# Schaltplan-LED.net
KiCad netlist of a schematic drawn in EAGLE
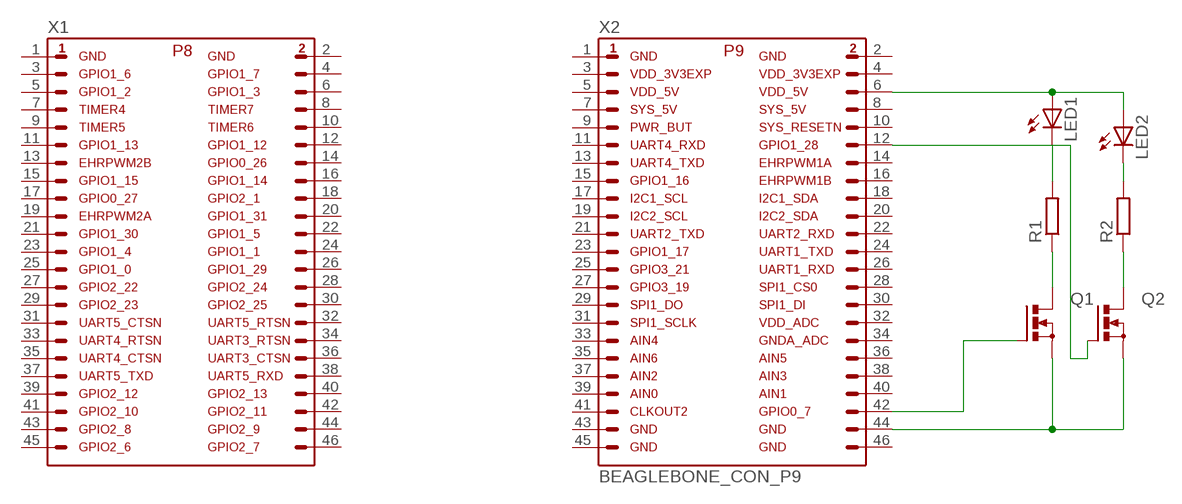
[diagram p0: schematic, sheet 1]

(export (version "E")
  (design (tool "Eeschema 10.0.6"))
  (components
    (comp (ref "LED1")
      (value "LEDCHIP-LED0603")
      (footprint "eagle-import:CHIP-LED0603")
      (libsource (lib "eagle-import") (part "LEDCHIP-LED0603"))
    )
    (comp (ref "LED2")
      (value "LEDCHIP-LED0603")
      (footprint "eagle-import:CHIP-LED0603")
      (libsource (lib "eagle-import") (part "LEDCHIP-LED0603"))
    )
    (comp (ref "Q1")
      (value "N-MOSFET-SO8S")
      (footprint "eagle-import:SO-08")
      (libsource (lib "eagle-import") (part "N-MOSFET-SO8S"))
    )
    (comp (ref "Q2")
      (value "N-MOSFET-SO8S")
      (footprint "eagle-import:SO-08")
      (libsource (lib "eagle-import") (part "N-MOSFET-SO8S"))
    )
    (comp (ref "R1")
      (value "R-EU_R0603")
      (footprint "eagle-import:R0603")
      (libsource (lib "eagle-import") (part "R-EU_R0603"))
    )
    (comp (ref "R2")
      (value "R-EU_R0603")
      (footprint "eagle-import:R0603")
      (libsource (lib "eagle-import") (part "R-EU_R0603"))
    )
    (comp (ref "X1")
      (value "BEAGLEBONE_CON_P8")
      (footprint "eagle-import:23X2_2-54")
      (libsource (lib "eagle-import") (part "BEAGLEBONE_CON_P8"))
    )
    (comp (ref "X2")
      (value "BEAGLEBONE_CON_P9")
      (footprint "eagle-import:23X2_2-54")
      (libsource (lib "eagle-import") (part "BEAGLEBONE_CON_P9"))
    )
  )
  (nets
    (net (code "1") (name "Net-(LED1-PadA)") (class "Default")
      (node (ref "LED1") (pin "A") (pinfunction "A_A") (pintype "passive"))
      (node (ref "LED2") (pin "A") (pinfunction "A_A") (pintype "passive"))
      (node (ref "X2") (pin "6") (pinfunction "6_6") (pintype "passive"))
    )
    (net (code "2") (name "Net-(LED1-PadC)") (class "Default")
      (node (ref "LED1") (pin "C") (pinfunction "C_C") (pintype "passive"))
      (node (ref "R1") (pin "2") (pinfunction "2_2") (pintype "passive"))
    )
    (net (code "3") (name "Net-(LED2-PadC)") (class "Default")
      (node (ref "LED2") (pin "C") (pinfunction "C_C") (pintype "passive"))
      (node (ref "R2") (pin "2") (pinfunction "2_2") (pintype "passive"))
    )
    (net (code "4") (name "Net-(Q1-D-Pad5)") (class "Default")
      (node (ref "Q1") (pin "5") (pinfunction "D_5") (pintype "passive"))
      (node (ref "Q1") (pin "6") (pinfunction "D_6") (pintype "passive"))
      (node (ref "Q1") (pin "7") (pinfunction "D_7") (pintype "passive"))
      (node (ref "Q1") (pin "8") (pinfunction "D_8") (pintype "passive"))
      (node (ref "R1") (pin "1") (pinfunction "1_1") (pintype "passive"))
    )
    (net (code "5") (name "Net-(Q1-G)") (class "Default")
      (node (ref "Q1") (pin "4") (pinfunction "G_4") (pintype "passive"))
      (node (ref "X2") (pin "42") (pinfunction "42_42") (pintype "passive"))
    )
    (net (code "6") (name "Net-(Q1-S-Pad1)") (class "Default")
      (node (ref "Q1") (pin "1") (pinfunction "S_1") (pintype "passive"))
      (node (ref "Q1") (pin "2") (pinfunction "S_2") (pintype "passive"))
      (node (ref "Q1") (pin "3") (pinfunction "S_3") (pintype "passive"))
      (node (ref "Q2") (pin "1") (pinfunction "S_1") (pintype "passive"))
      (node (ref "Q2") (pin "2") (pinfunction "S_2") (pintype "passive"))
      (node (ref "Q2") (pin "3") (pinfunction "S_3") (pintype "passive"))
      (node (ref "X2") (pin "44") (pinfunction "44_44") (pintype "passive"))
    )
    (net (code "7") (name "Net-(Q2-D-Pad5)") (class "Default")
      (node (ref "Q2") (pin "5") (pinfunction "D_5") (pintype "passive"))
      (node (ref "Q2") (pin "6") (pinfunction "D_6") (pintype "passive"))
      (node (ref "Q2") (pin "7") (pinfunction "D_7") (pintype "passive"))
      (node (ref "Q2") (pin "8") (pinfunction "D_8") (pintype "passive"))
      (node (ref "R2") (pin "1") (pinfunction "1_1") (pintype "passive"))
    )
    (net (code "8") (name "Net-(Q2-G)") (class "Default")
      (node (ref "Q2") (pin "4") (pinfunction "G_4") (pintype "passive"))
      (node (ref "X2") (pin "12") (pinfunction "12_12") (pintype "passive"))
    )
    (net (code "9") (name "unconnected-(X1-Pad1)") (class "Default")
      (node (ref "X1") (pin "1") (pinfunction "1_1") (pintype "passive"))
    )
    (net (code "10") (name "unconnected-(X1-Pad2)") (class "Default")
      (node (ref "X1") (pin "2") (pinfunction "2_2") (pintype "passive"))
    )
    (net (code "11") (name "unconnected-(X1-Pad3)") (class "Default")
      (node (ref "X1") (pin "3") (pinfunction "3_3") (pintype "passive"))
    )
    (net (code "12") (name "unconnected-(X1-Pad4)") (class "Default")
      (node (ref "X1") (pin "4") (pinfunction "4_4") (pintype "passive"))
    )
    (net (code "13") (name "unconnected-(X1-Pad5)") (class "Default")
      (node (ref "X1") (pin "5") (pinfunction "5_5") (pintype "passive"))
    )
    (net (code "14") (name "unconnected-(X1-Pad6)") (class "Default")
      (node (ref "X1") (pin "6") (pinfunction "6_6") (pintype "passive"))
    )
    (net (code "15") (name "unconnected-(X1-Pad7)") (class "Default")
      (node (ref "X1") (pin "7") (pinfunction "7_7") (pintype "passive"))
    )
    (net (code "16") (name "unconnected-(X1-Pad8)") (class "Default")
      (node (ref "X1") (pin "8") (pinfunction "8_8") (pintype "passive"))
    )
    (net (code "17") (name "unconnected-(X1-Pad9)") (class "Default")
      (node (ref "X1") (pin "9") (pinfunction "9_9") (pintype "passive"))
    )
    (net (code "18") (name "unconnected-(X1-Pad10)") (class "Default")
      (node (ref "X1") (pin "10") (pinfunction "10_10") (pintype "passive"))
    )
    (net (code "19") (name "unconnected-(X1-Pad11)") (class "Default")
      (node (ref "X1") (pin "11") (pinfunction "11_11") (pintype "passive"))
    )
    (net (code "20") (name "unconnected-(X1-Pad12)") (class "Default")
      (node (ref "X1") (pin "12") (pinfunction "12_12") (pintype "passive"))
    )
    (net (code "21") (name "unconnected-(X1-Pad13)") (class "Default")
      (node (ref "X1") (pin "13") (pinfunction "13_13") (pintype "passive"))
    )
    (net (code "22") (name "unconnected-(X1-Pad14)") (class "Default")
      (node (ref "X1") (pin "14") (pinfunction "14_14") (pintype "passive"))
    )
    (net (code "23") (name "unconnected-(X1-Pad15)") (class "Default")
      (node (ref "X1") (pin "15") (pinfunction "15_15") (pintype "passive"))
    )
    (net (code "24") (name "unconnected-(X1-Pad16)") (class "Default")
      (node (ref "X1") (pin "16") (pinfunction "16_16") (pintype "passive"))
    )
    (net (code "25") (name "unconnected-(X1-Pad17)") (class "Default")
      (node (ref "X1") (pin "17") (pinfunction "17_17") (pintype "passive"))
    )
    (net (code "26") (name "unconnected-(X1-Pad18)") (class "Default")
      (node (ref "X1") (pin "18") (pinfunction "18_18") (pintype "passive"))
    )
    (net (code "27") (name "unconnected-(X1-Pad19)") (class "Default")
      (node (ref "X1") (pin "19") (pinfunction "19_19") (pintype "passive"))
    )
    (net (code "28") (name "unconnected-(X1-Pad20)") (class "Default")
      (node (ref "X1") (pin "20") (pinfunction "20_20") (pintype "passive"))
    )
    (net (code "29") (name "unconnected-(X1-Pad21)") (class "Default")
      (node (ref "X1") (pin "21") (pinfunction "21_21") (pintype "passive"))
    )
    (net (code "30") (name "unconnected-(X1-Pad22)") (class "Default")
      (node (ref "X1") (pin "22") (pinfunction "22_22") (pintype "passive"))
    )
    (net (code "31") (name "unconnected-(X1-Pad23)") (class "Default")
      (node (ref "X1") (pin "23") (pinfunction "23_23") (pintype "passive"))
    )
    (net (code "32") (name "unconnected-(X1-Pad24)") (class "Default")
      (node (ref "X1") (pin "24") (pinfunction "24_24") (pintype "passive"))
    )
    (net (code "33") (name "unconnected-(X1-Pad25)") (class "Default")
      (node (ref "X1") (pin "25") (pinfunction "25_25") (pintype "passive"))
    )
    (net (code "34") (name "unconnected-(X1-Pad26)") (class "Default")
      (node (ref "X1") (pin "26") (pinfunction "26_26") (pintype "passive"))
    )
    (net (code "35") (name "unconnected-(X1-Pad27)") (class "Default")
      (node (ref "X1") (pin "27") (pinfunction "27_27") (pintype "passive"))
    )
    (net (code "36") (name "unconnected-(X1-Pad28)") (class "Default")
      (node (ref "X1") (pin "28") (pinfunction "28_28") (pintype "passive"))
    )
    (net (code "37") (name "unconnected-(X1-Pad29)") (class "Default")
      (node (ref "X1") (pin "29") (pinfunction "29_29") (pintype "passive"))
    )
    (net (code "38") (name "unconnected-(X1-Pad30)") (class "Default")
      (node (ref "X1") (pin "30") (pinfunction "30_30") (pintype "passive"))
    )
    (net (code "39") (name "unconnected-(X1-Pad31)") (class "Default")
      (node (ref "X1") (pin "31") (pinfunction "31_31") (pintype "passive"))
    )
    (net (code "40") (name "unconnected-(X1-Pad32)") (class "Default")
      (node (ref "X1") (pin "32") (pinfunction "32_32") (pintype "passive"))
    )
    (net (code "41") (name "unconnected-(X1-Pad33)") (class "Default")
      (node (ref "X1") (pin "33") (pinfunction "33_33") (pintype "passive"))
    )
    (net (code "42") (name "unconnected-(X1-Pad34)") (class "Default")
      (node (ref "X1") (pin "34") (pinfunction "34_34") (pintype "passive"))
    )
    (net (code "43") (name "unconnected-(X1-Pad35)") (class "Default")
      (node (ref "X1") (pin "35") (pinfunction "35_35") (pintype "passive"))
    )
    (net (code "44") (name "unconnected-(X1-Pad36)") (class "Default")
      (node (ref "X1") (pin "36") (pinfunction "36_36") (pintype "passive"))
    )
    (net (code "45") (name "unconnected-(X1-Pad37)") (class "Default")
      (node (ref "X1") (pin "37") (pinfunction "37_37") (pintype "passive"))
    )
    (net (code "46") (name "unconnected-(X1-Pad38)") (class "Default")
      (node (ref "X1") (pin "38") (pinfunction "38_38") (pintype "passive"))
    )
    (net (code "47") (name "unconnected-(X1-Pad39)") (class "Default")
      (node (ref "X1") (pin "39") (pinfunction "39_39") (pintype "passive"))
    )
    (net (code "48") (name "unconnected-(X1-Pad40)") (class "Default")
      (node (ref "X1") (pin "40") (pinfunction "40_40") (pintype "passive"))
    )
    (net (code "49") (name "unconnected-(X1-Pad41)") (class "Default")
      (node (ref "X1") (pin "41") (pinfunction "41_41") (pintype "passive"))
    )
    (net (code "50") (name "unconnected-(X1-Pad42)") (class "Default")
      (node (ref "X1") (pin "42") (pinfunction "42_42") (pintype "passive"))
    )
    (net (code "51") (name "unconnected-(X1-Pad43)") (class "Default")
      (node (ref "X1") (pin "43") (pinfunction "43_43") (pintype "passive"))
    )
    (net (code "52") (name "unconnected-(X1-Pad44)") (class "Default")
      (node (ref "X1") (pin "44") (pinfunction "44_44") (pintype "passive"))
    )
    (net (code "53") (name "unconnected-(X1-Pad45)") (class "Default")
      (node (ref "X1") (pin "45") (pinfunction "45_45") (pintype "passive"))
    )
    (net (code "54") (name "unconnected-(X1-Pad46)") (class "Default")
      (node (ref "X1") (pin "46") (pinfunction "46_46") (pintype "passive"))
    )
    (net (code "55") (name "unconnected-(X2-Pad1)") (class "Default")
      (node (ref "X2") (pin "1") (pinfunction "1_1") (pintype "passive"))
    )
    (net (code "56") (name "unconnected-(X2-Pad2)") (class "Default")
      (node (ref "X2") (pin "2") (pinfunction "2_2") (pintype "passive"))
    )
    (net (code "57") (name "unconnected-(X2-Pad3)") (class "Default")
      (node (ref "X2") (pin "3") (pinfunction "3_3") (pintype "passive"))
    )
    (net (code "58") (name "unconnected-(X2-Pad4)") (class "Default")
      (node (ref "X2") (pin "4") (pinfunction "4_4") (pintype "passive"))
    )
    (net (code "59") (name "unconnected-(X2-Pad5)") (class "Default")
      (node (ref "X2") (pin "5") (pinfunction "5_5") (pintype "passive"))
    )
    (net (code "60") (name "unconnected-(X2-Pad7)") (class "Default")
      (node (ref "X2") (pin "7") (pinfunction "7_7") (pintype "passive"))
    )
    (net (code "61") (name "unconnected-(X2-Pad8)") (class "Default")
      (node (ref "X2") (pin "8") (pinfunction "8_8") (pintype "passive"))
    )
    (net (code "62") (name "unconnected-(X2-Pad9)") (class "Default")
      (node (ref "X2") (pin "9") (pinfunction "9_9") (pintype "passive"))
    )
    (net (code "63") (name "unconnected-(X2-Pad10)") (class "Default")
      (node (ref "X2") (pin "10") (pinfunction "10_10") (pintype "passive"))
    )
    (net (code "64") (name "unconnected-(X2-Pad11)") (class "Default")
      (node (ref "X2") (pin "11") (pinfunction "11_11") (pintype "passive"))
    )
    (net (code "65") (name "unconnected-(X2-Pad13)") (class "Default")
      (node (ref "X2") (pin "13") (pinfunction "13_13") (pintype "passive"))
    )
    (net (code "66") (name "unconnected-(X2-Pad14)") (class "Default")
      (node (ref "X2") (pin "14") (pinfunction "14_14") (pintype "passive"))
    )
    (net (code "67") (name "unconnected-(X2-Pad15)") (class "Default")
      (node (ref "X2") (pin "15") (pinfunction "15_15") (pintype "passive"))
    )
    (net (code "68") (name "unconnected-(X2-Pad16)") (class "Default")
      (node (ref "X2") (pin "16") (pinfunction "16_16") (pintype "passive"))
    )
    (net (code "69") (name "unconnected-(X2-Pad17)") (class "Default")
      (node (ref "X2") (pin "17") (pinfunction "17_17") (pintype "passive"))
    )
    (net (code "70") (name "unconnected-(X2-Pad18)") (class "Default")
      (node (ref "X2") (pin "18") (pinfunction "18_18") (pintype "passive"))
    )
    (net (code "71") (name "unconnected-(X2-Pad19)") (class "Default")
      (node (ref "X2") (pin "19") (pinfunction "19_19") (pintype "passive"))
    )
    (net (code "72") (name "unconnected-(X2-Pad20)") (class "Default")
      (node (ref "X2") (pin "20") (pinfunction "20_20") (pintype "passive"))
    )
    (net (code "73") (name "unconnected-(X2-Pad21)") (class "Default")
      (node (ref "X2") (pin "21") (pinfunction "21_21") (pintype "passive"))
    )
    (net (code "74") (name "unconnected-(X2-Pad22)") (class "Default")
      (node (ref "X2") (pin "22") (pinfunction "22_22") (pintype "passive"))
    )
    (net (code "75") (name "unconnected-(X2-Pad23)") (class "Default")
      (node (ref "X2") (pin "23") (pinfunction "23_23") (pintype "passive"))
    )
    (net (code "76") (name "unconnected-(X2-Pad24)") (class "Default")
      (node (ref "X2") (pin "24") (pinfunction "24_24") (pintype "passive"))
    )
    (net (code "77") (name "unconnected-(X2-Pad25)") (class "Default")
      (node (ref "X2") (pin "25") (pinfunction "25_25") (pintype "passive"))
    )
    (net (code "78") (name "unconnected-(X2-Pad26)") (class "Default")
      (node (ref "X2") (pin "26") (pinfunction "26_26") (pintype "passive"))
    )
    (net (code "79") (name "unconnected-(X2-Pad27)") (class "Default")
      (node (ref "X2") (pin "27") (pinfunction "27_27") (pintype "passive"))
    )
    (net (code "80") (name "unconnected-(X2-Pad28)") (class "Default")
      (node (ref "X2") (pin "28") (pinfunction "28_28") (pintype "passive"))
    )
    (net (code "81") (name "unconnected-(X2-Pad29)") (class "Default")
      (node (ref "X2") (pin "29") (pinfunction "29_29") (pintype "passive"))
    )
    (net (code "82") (name "unconnected-(X2-Pad30)") (class "Default")
      (node (ref "X2") (pin "30") (pinfunction "30_30") (pintype "passive"))
    )
    (net (code "83") (name "unconnected-(X2-Pad31)") (class "Default")
      (node (ref "X2") (pin "31") (pinfunction "31_31") (pintype "passive"))
    )
    (net (code "84") (name "unconnected-(X2-Pad32)") (class "Default")
      (node (ref "X2") (pin "32") (pinfunction "32_32") (pintype "passive"))
    )
    (net (code "85") (name "unconnected-(X2-Pad33)") (class "Default")
      (node (ref "X2") (pin "33") (pinfunction "33_33") (pintype "passive"))
    )
    (net (code "86") (name "unconnected-(X2-Pad34)") (class "Default")
      (node (ref "X2") (pin "34") (pinfunction "34_34") (pintype "passive"))
    )
    (net (code "87") (name "unconnected-(X2-Pad35)") (class "Default")
      (node (ref "X2") (pin "35") (pinfunction "35_35") (pintype "passive"))
    )
    (net (code "88") (name "unconnected-(X2-Pad36)") (class "Default")
      (node (ref "X2") (pin "36") (pinfunction "36_36") (pintype "passive"))
    )
    (net (code "89") (name "unconnected-(X2-Pad37)") (class "Default")
      (node (ref "X2") (pin "37") (pinfunction "37_37") (pintype "passive"))
    )
    (net (code "90") (name "unconnected-(X2-Pad38)") (class "Default")
      (node (ref "X2") (pin "38") (pinfunction "38_38") (pintype "passive"))
    )
    (net (code "91") (name "unconnected-(X2-Pad39)") (class "Default")
      (node (ref "X2") (pin "39") (pinfunction "39_39") (pintype "passive"))
    )
    (net (code "92") (name "unconnected-(X2-Pad40)") (class "Default")
      (node (ref "X2") (pin "40") (pinfunction "40_40") (pintype "passive"))
    )
    (net (code "93") (name "unconnected-(X2-Pad41)") (class "Default")
      (node (ref "X2") (pin "41") (pinfunction "41_41") (pintype "passive"))
    )
    (net (code "94") (name "unconnected-(X2-Pad43)") (class "Default")
      (node (ref "X2") (pin "43") (pinfunction "43_43") (pintype "passive"))
    )
    (net (code "95") (name "unconnected-(X2-Pad45)") (class "Default")
      (node (ref "X2") (pin "45") (pinfunction "45_45") (pintype "passive"))
    )
    (net (code "96") (name "unconnected-(X2-Pad46)") (class "Default")
      (node (ref "X2") (pin "46") (pinfunction "46_46") (pintype "passive"))
    )
  )
)
